# ProcessorBoard_STM32F103C.net
KiCad netlist of a schematic drawn in Altium Designer
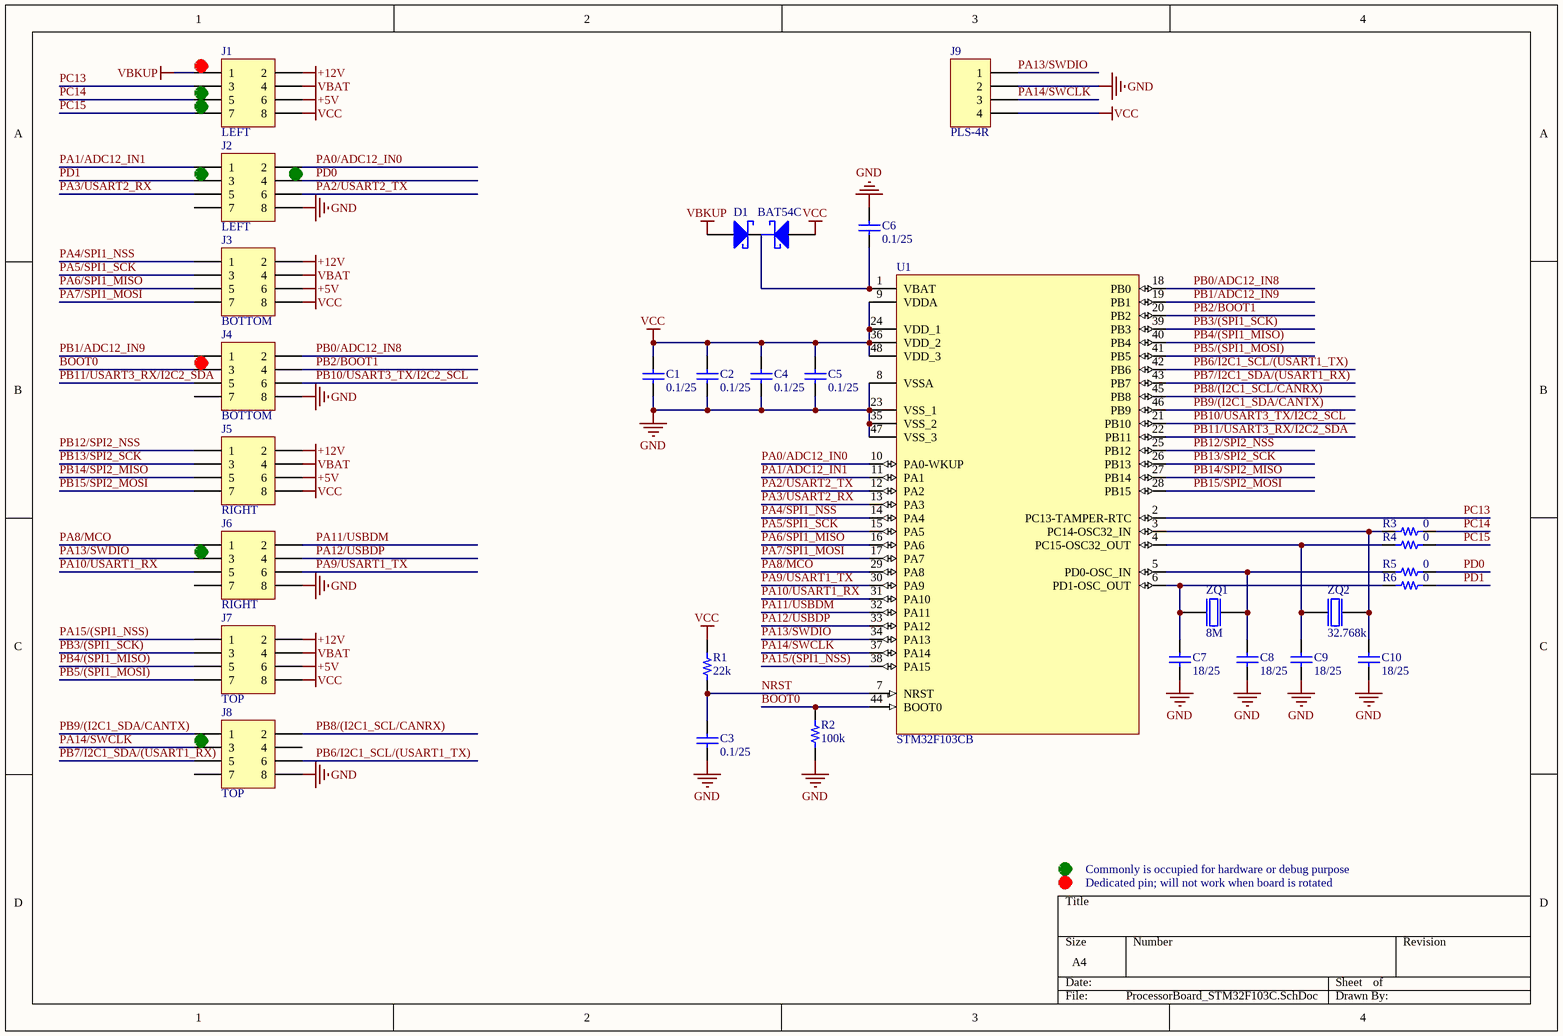
[diagram p0: ProcessorBoard_STM32F103C.SchDoc]

(export (version "E")
  (design (tool "Eeschema 10.0.6"))
  (components
    (comp (ref "C1")
      (value "0.1/25")
      (footprint "CAP0402")
      (description "Ceramic chip capacitor 0402")
      (fields
        (field (name "PARTNUMBER") "CAP0402")
        (field (name "VOLTAGE") "25")
        (field (name "AUTHOR") "oiezhov")
      )
      (libsource (lib "Library") (part "Capacitor"))
    )
    (comp (ref "C2")
      (value "0.1/25")
      (footprint "CAP0402")
      (description "Ceramic chip capacitor 0402")
      (fields
        (field (name "PARTNUMBER") "CAP0402")
        (field (name "VOLTAGE") "25")
        (field (name "AUTHOR") "oiezhov")
      )
      (libsource (lib "Library") (part "Capacitor"))
    )
    (comp (ref "C3")
      (value "0.1/25")
      (footprint "CAP0402")
      (description "Ceramic chip capacitor 0402")
      (fields
        (field (name "PARTNUMBER") "CAP0402")
        (field (name "VOLTAGE") "25")
        (field (name "AUTHOR") "oiezhov")
      )
      (libsource (lib "Library") (part "Capacitor"))
    )
    (comp (ref "C4")
      (value "0.1/25")
      (footprint "CAP0402")
      (description "Ceramic chip capacitor 0402")
      (fields
        (field (name "PARTNUMBER") "CAP0402")
        (field (name "VOLTAGE") "25")
        (field (name "AUTHOR") "oiezhov")
      )
      (libsource (lib "Library") (part "Capacitor"))
    )
    (comp (ref "C5")
      (value "0.1/25")
      (footprint "CAP0402")
      (description "Ceramic chip capacitor 0402")
      (fields
        (field (name "PARTNUMBER") "CAP0402")
        (field (name "VOLTAGE") "25")
        (field (name "AUTHOR") "oiezhov")
      )
      (libsource (lib "Library") (part "Capacitor"))
    )
    (comp (ref "C6")
      (value "0.1/25")
      (footprint "CAP0402")
      (description "Ceramic chip capacitor 0402")
      (fields
        (field (name "PARTNUMBER") "CAP0402")
        (field (name "VOLTAGE") "25")
        (field (name "AUTHOR") "oiezhov")
      )
      (libsource (lib "Library") (part "Capacitor"))
    )
    (comp (ref "C7")
      (value "18/25")
      (footprint "CAP0402")
      (description "Ceramic chip capacitor 0402")
      (fields
        (field (name "PARTNUMBER") "CAP0402")
        (field (name "VOLTAGE") "25")
        (field (name "AUTHOR") "oiezhov")
      )
      (libsource (lib "Library") (part "Capacitor"))
    )
    (comp (ref "C8")
      (value "18/25")
      (footprint "CAP0402")
      (description "Ceramic chip capacitor 0402")
      (fields
        (field (name "PARTNUMBER") "CAP0402")
        (field (name "VOLTAGE") "25")
        (field (name "AUTHOR") "oiezhov")
      )
      (libsource (lib "Library") (part "Capacitor"))
    )
    (comp (ref "C9")
      (value "18/25")
      (footprint "CAP0402")
      (description "Ceramic chip capacitor 0402")
      (fields
        (field (name "PARTNUMBER") "CAP0402")
        (field (name "VOLTAGE") "25")
        (field (name "AUTHOR") "oiezhov")
      )
      (libsource (lib "Library") (part "Capacitor"))
    )
    (comp (ref "C10")
      (value "18/25")
      (footprint "CAP0402")
      (description "Ceramic chip capacitor 0402")
      (fields
        (field (name "PARTNUMBER") "CAP0402")
        (field (name "VOLTAGE") "25")
        (field (name "AUTHOR") "oiezhov")
      )
      (libsource (lib "Library") (part "Capacitor"))
    )
    (comp (ref "D1")
      (value "BAT54C")
      (footprint "SOT23")
      (description "Schottky diode")
      (fields (field (name "AUTHOR") "oiezhov"))
      (libsource (lib "Library") (part "2x Schottky (A-CC-A)"))
    )
    (comp (ref "J1")
      (value "LEFT")
      (footprint "PBDM-8")
      (description "2x4-pin header, pitch 2.54 mm")
      (fields (field (name "PARTNUMBER") "PBDM-8") (field (name "AUTHOR") "oiezhov"))
      (libsource (lib "Library") (part "8-pin dual row connector"))
    )
    (comp (ref "J2")
      (value "LEFT")
      (footprint "PBDM-8")
      (description "2x4-pin header, pitch 2.54 mm")
      (fields (field (name "PARTNUMBER") "PBDM-8") (field (name "AUTHOR") "oiezhov"))
      (libsource (lib "Library") (part "8-pin dual row connector"))
    )
    (comp (ref "J3")
      (value "BOTTOM")
      (footprint "PBDM-8")
      (description "2x4-pin header, pitch 2.54 mm")
      (fields (field (name "PARTNUMBER") "PBDM-8") (field (name "AUTHOR") "oiezhov"))
      (libsource (lib "Library") (part "8-pin dual row connector"))
    )
    (comp (ref "J4")
      (value "BOTTOM")
      (footprint "PBDM-8")
      (description "2x4-pin header, pitch 2.54 mm")
      (fields (field (name "PARTNUMBER") "PBDM-8") (field (name "AUTHOR") "oiezhov"))
      (libsource (lib "Library") (part "8-pin dual row connector"))
    )
    (comp (ref "J5")
      (value "RIGHT")
      (footprint "PBDM-8")
      (description "2x4-pin header, pitch 2.54 mm")
      (fields (field (name "PARTNUMBER") "PBDM-8") (field (name "AUTHOR") "oiezhov"))
      (libsource (lib "Library") (part "8-pin dual row connector"))
    )
    (comp (ref "J6")
      (value "RIGHT")
      (footprint "PBDM-8")
      (description "2x4-pin header, pitch 2.54 mm")
      (fields (field (name "PARTNUMBER") "PBDM-8") (field (name "AUTHOR") "oiezhov"))
      (libsource (lib "Library") (part "8-pin dual row connector"))
    )
    (comp (ref "J7")
      (value "TOP")
      (footprint "PBDM-8")
      (description "2x4-pin header, pitch 2.54 mm")
      (fields (field (name "PARTNUMBER") "PBDM-8") (field (name "AUTHOR") "oiezhov"))
      (libsource (lib "Library") (part "8-pin dual row connector"))
    )
    (comp (ref "J8")
      (value "TOP")
      (footprint "PBDM-8")
      (description "2x4-pin header, pitch 2.54 mm")
      (fields (field (name "PARTNUMBER") "PBDM-8") (field (name "AUTHOR") "oiezhov"))
      (libsource (lib "Library") (part "8-pin dual row connector"))
    )
    (comp (ref "J9")
      (value "PLS-4R")
      (footprint "PLS-4R")
      (description "4-pin angle header, pitch 2.54 mm")
      (fields (field (name "AUTHOR") "oiezhov"))
      (libsource (lib "Library") (part "4-pin connector"))
    )
    (comp (ref "R1")
      (value "22k")
      (footprint "RES0402")
      (description "Ceramic chip resistor")
      (fields (field (name "PARTNUMBER") "RES0402") (field (name "AUTHOR") "oiezhov"))
      (libsource (lib "Library") (part "Resistor"))
    )
    (comp (ref "R2")
      (value "100k")
      (footprint "RES0402")
      (description "Ceramic chip resistor")
      (fields (field (name "PARTNUMBER") "RES0402") (field (name "AUTHOR") "oiezhov"))
      (libsource (lib "Library") (part "Resistor"))
    )
    (comp (ref "R3")
      (value "0")
      (footprint "RES0402")
      (description "Ceramic chip resistor")
      (fields (field (name "PARTNUMBER") "RES0402") (field (name "AUTHOR") "oiezhov"))
      (libsource (lib "Library") (part "Resistor"))
    )
    (comp (ref "R4")
      (value "0")
      (footprint "RES0402")
      (description "Ceramic chip resistor")
      (fields (field (name "PARTNUMBER") "RES0402") (field (name "AUTHOR") "oiezhov"))
      (libsource (lib "Library") (part "Resistor"))
    )
    (comp (ref "R5")
      (value "0")
      (footprint "RES0402")
      (description "Ceramic chip resistor")
      (fields (field (name "PARTNUMBER") "RES0402") (field (name "AUTHOR") "oiezhov"))
      (libsource (lib "Library") (part "Resistor"))
    )
    (comp (ref "R6")
      (value "0")
      (footprint "RES0402")
      (description "Ceramic chip resistor")
      (fields (field (name "PARTNUMBER") "RES0402") (field (name "AUTHOR") "oiezhov"))
      (libsource (lib "Library") (part "Resistor"))
    )
    (comp (ref "U1")
      (value "STM32F103CB")
      (footprint "LQFP48")
      (description "General purpose 32-bit microcontroller")
      (fields (field (name "AUTHOR") "oiezhov"))
      (libsource (lib "Library") (part "STM32F103C"))
    )
    (comp (ref "ZQ1")
      (value "8M")
      (footprint "HC49/U3H")
      (description "Quartz crystal in low profile package")
      (fields (field (name "PARTNUMBER") "KX-3H") (field (name "AUTHOR") "oiezhov"))
      (libsource (lib "Library") (part "Quartz crystal"))
    )
    (comp (ref "ZQ2")
      (value "32.768k")
      (footprint "D6.2x2")
      (description "Quartz crystal in cylindrical package")
      (fields (field (name "PARTNUMBER") "KX-26") (field (name "AUTHOR") "oiezhov"))
      (libsource (lib "Library") (part "Quartz crystal"))
    )
  )
  (nets
    (net (code "1") (name "+5V") (class "Default")
      (node (ref "J1") (pin "6") (pinfunction "6_6") (pintype "passive"))
      (node (ref "J3") (pin "6") (pinfunction "6_6") (pintype "passive"))
      (node (ref "J5") (pin "6") (pinfunction "6_6") (pintype "passive"))
      (node (ref "J7") (pin "6") (pinfunction "6_6") (pintype "passive"))
    )
    (net (code "2") (name "+12V") (class "Default")
      (node (ref "J1") (pin "2") (pinfunction "2_2") (pintype "passive"))
      (node (ref "J3") (pin "2") (pinfunction "2_2") (pintype "passive"))
      (node (ref "J5") (pin "2") (pinfunction "2_2") (pintype "passive"))
      (node (ref "J7") (pin "2") (pinfunction "2_2") (pintype "passive"))
    )
    (net (code "3") (name "/BOOT0") (class "Default")
      (node (ref "J4") (pin "3") (pinfunction "3_3") (pintype "passive"))
      (node (ref "R2") (pin "2") (pinfunction "2_2") (pintype "passive"))
      (node (ref "U1") (pin "44") (pinfunction "BOOT0_44") (pintype "input"))
    )
    (net (code "4") (name "/NRST") (class "Default")
      (node (ref "C3") (pin "2") (pinfunction "2_2") (pintype "passive"))
      (node (ref "R1") (pin "1") (pinfunction "1_1") (pintype "passive"))
      (node (ref "U1") (pin "7") (pinfunction "NRST_7") (pintype "input"))
    )
    (net (code "5") (name "/PA0{slash}ADC12_IN0") (class "Default")
      (node (ref "J2") (pin "2") (pinfunction "2_2") (pintype "passive"))
      (node (ref "U1") (pin "10") (pinfunction "PA0-WKUP_10") (pintype "bidirectional"))
    )
    (net (code "6") (name "/PA1{slash}ADC12_IN1") (class "Default")
      (node (ref "J2") (pin "1") (pinfunction "1_1") (pintype "passive"))
      (node (ref "U1") (pin "11") (pinfunction "PA1_11") (pintype "bidirectional"))
    )
    (net (code "7") (name "/PA2{slash}USART2_TX") (class "Default")
      (node (ref "J2") (pin "6") (pinfunction "6_6") (pintype "passive"))
      (node (ref "U1") (pin "12") (pinfunction "PA2_12") (pintype "bidirectional"))
    )
    (net (code "8") (name "/PA3{slash}USART2_RX") (class "Default")
      (node (ref "J2") (pin "5") (pinfunction "5_5") (pintype "passive"))
      (node (ref "U1") (pin "13") (pinfunction "PA3_13") (pintype "bidirectional"))
    )
    (net (code "9") (name "/PA4{slash}SPI1_NSS") (class "Default")
      (node (ref "J3") (pin "1") (pinfunction "1_1") (pintype "passive"))
      (node (ref "U1") (pin "14") (pinfunction "PA4_14") (pintype "bidirectional"))
    )
    (net (code "10") (name "/PA5{slash}SPI1_SCK") (class "Default")
      (node (ref "J3") (pin "3") (pinfunction "3_3") (pintype "passive"))
      (node (ref "U1") (pin "15") (pinfunction "PA5_15") (pintype "bidirectional"))
    )
    (net (code "11") (name "/PA6{slash}SPI1_MISO") (class "Default")
      (node (ref "J3") (pin "5") (pinfunction "5_5") (pintype "passive"))
      (node (ref "U1") (pin "16") (pinfunction "PA6_16") (pintype "bidirectional"))
    )
    (net (code "12") (name "/PA7{slash}SPI1_MOSI") (class "Default")
      (node (ref "J3") (pin "7") (pinfunction "7_7") (pintype "passive"))
      (node (ref "U1") (pin "17") (pinfunction "PA7_17") (pintype "bidirectional"))
    )
    (net (code "13") (name "/PA8{slash}MCO") (class "Default")
      (node (ref "J6") (pin "1") (pinfunction "1_1") (pintype "passive"))
      (node (ref "U1") (pin "29") (pinfunction "PA8_29") (pintype "bidirectional"))
    )
    (net (code "14") (name "/PA9{slash}USART1_TX") (class "Default")
      (node (ref "J6") (pin "6") (pinfunction "6_6") (pintype "passive"))
      (node (ref "U1") (pin "30") (pinfunction "PA9_30") (pintype "bidirectional"))
    )
    (net (code "15") (name "/PA10{slash}USART1_RX") (class "Default")
      (node (ref "J6") (pin "5") (pinfunction "5_5") (pintype "passive"))
      (node (ref "U1") (pin "31") (pinfunction "PA10_31") (pintype "bidirectional"))
    )
    (net (code "16") (name "/PA11{slash}USBDM") (class "Default")
      (node (ref "J6") (pin "2") (pinfunction "2_2") (pintype "passive"))
      (node (ref "U1") (pin "32") (pinfunction "PA11_32") (pintype "bidirectional"))
    )
    (net (code "17") (name "/PA12{slash}USBDP") (class "Default")
      (node (ref "J6") (pin "4") (pinfunction "4_4") (pintype "passive"))
      (node (ref "U1") (pin "33") (pinfunction "PA12_33") (pintype "bidirectional"))
    )
    (net (code "18") (name "/PA13{slash}SWDIO") (class "Default")
      (node (ref "J6") (pin "3") (pinfunction "3_3") (pintype "passive"))
      (node (ref "J9") (pin "1") (pinfunction "1_1") (pintype "passive"))
      (node (ref "U1") (pin "34") (pinfunction "PA13_34") (pintype "bidirectional"))
    )
    (net (code "19") (name "/PA14{slash}SWCLK") (class "Default")
      (node (ref "J8") (pin "3") (pinfunction "3_3") (pintype "passive"))
      (node (ref "J9") (pin "3") (pinfunction "3_3") (pintype "passive"))
      (node (ref "U1") (pin "37") (pinfunction "PA14_37") (pintype "bidirectional"))
    )
    (net (code "20") (name "/PA15{slash}(SPI1_NSS)") (class "Default")
      (node (ref "J7") (pin "1") (pinfunction "1_1") (pintype "passive"))
      (node (ref "U1") (pin "38") (pinfunction "PA15_38") (pintype "bidirectional"))
    )
    (net (code "21") (name "/PB0{slash}ADC12_IN8") (class "Default")
      (node (ref "J4") (pin "2") (pinfunction "2_2") (pintype "passive"))
      (node (ref "U1") (pin "18") (pinfunction "PB0_18") (pintype "bidirectional"))
    )
    (net (code "22") (name "/PB1{slash}ADC12_IN9") (class "Default")
      (node (ref "J4") (pin "1") (pinfunction "1_1") (pintype "passive"))
      (node (ref "U1") (pin "19") (pinfunction "PB1_19") (pintype "bidirectional"))
    )
    (net (code "23") (name "/PB2{slash}BOOT1") (class "Default")
      (node (ref "J4") (pin "4") (pinfunction "4_4") (pintype "passive"))
      (node (ref "U1") (pin "20") (pinfunction "PB2_20") (pintype "bidirectional"))
    )
    (net (code "24") (name "/PB3{slash}(SPI1_SCK)") (class "Default")
      (node (ref "J7") (pin "3") (pinfunction "3_3") (pintype "passive"))
      (node (ref "U1") (pin "39") (pinfunction "PB3_39") (pintype "bidirectional"))
    )
    (net (code "25") (name "/PB4{slash}(SPI1_MISO)") (class "Default")
      (node (ref "J7") (pin "5") (pinfunction "5_5") (pintype "passive"))
      (node (ref "U1") (pin "40") (pinfunction "PB4_40") (pintype "bidirectional"))
    )
    (net (code "26") (name "/PB5{slash}(SPI1_MOSI)") (class "Default")
      (node (ref "J7") (pin "7") (pinfunction "7_7") (pintype "passive"))
      (node (ref "U1") (pin "41") (pinfunction "PB5_41") (pintype "bidirectional"))
    )
    (net (code "27") (name "/PB6{slash}I2C1_SCL{slash}(USART1_TX)") (class "Default")
      (node (ref "J8") (pin "6") (pinfunction "6_6") (pintype "passive"))
      (node (ref "U1") (pin "42") (pinfunction "PB6_42") (pintype "bidirectional"))
    )
    (net (code "28") (name "/PB7{slash}I2C1_SDA{slash}(USART1_RX)") (class "Default")
      (node (ref "J8") (pin "5") (pinfunction "5_5") (pintype "passive"))
      (node (ref "U1") (pin "43") (pinfunction "PB7_43") (pintype "bidirectional"))
    )
    (net (code "29") (name "/PB8{slash}(I2C1_SCL{slash}CANRX)") (class "Default")
      (node (ref "J8") (pin "2") (pinfunction "2_2") (pintype "passive"))
      (node (ref "U1") (pin "45") (pinfunction "PB8_45") (pintype "bidirectional"))
    )
    (net (code "30") (name "/PB9{slash}(I2C1_SDA{slash}CANTX)") (class "Default")
      (node (ref "J8") (pin "1") (pinfunction "1_1") (pintype "passive"))
      (node (ref "U1") (pin "46") (pinfunction "PB9_46") (pintype "bidirectional"))
    )
    (net (code "31") (name "/PB10{slash}USART3_TX{slash}I2C2_SCL") (class "Default")
      (node (ref "J4") (pin "6") (pinfunction "6_6") (pintype "passive"))
      (node (ref "U1") (pin "21") (pinfunction "PB10_21") (pintype "bidirectional"))
    )
    (net (code "32") (name "/PB11{slash}USART3_RX{slash}I2C2_SDA") (class "Default")
      (node (ref "J4") (pin "5") (pinfunction "5_5") (pintype "passive"))
      (node (ref "U1") (pin "22") (pinfunction "PB11_22") (pintype "bidirectional"))
    )
    (net (code "33") (name "/PB12{slash}SPI2_NSS") (class "Default")
      (node (ref "J5") (pin "1") (pinfunction "1_1") (pintype "passive"))
      (node (ref "U1") (pin "25") (pinfunction "PB12_25") (pintype "bidirectional"))
    )
    (net (code "34") (name "/PB13{slash}SPI2_SCK") (class "Default")
      (node (ref "J5") (pin "3") (pinfunction "3_3") (pintype "passive"))
      (node (ref "U1") (pin "26") (pinfunction "PB13_26") (pintype "bidirectional"))
    )
    (net (code "35") (name "/PB14{slash}SPI2_MISO") (class "Default")
      (node (ref "J5") (pin "5") (pinfunction "5_5") (pintype "passive"))
      (node (ref "U1") (pin "27") (pinfunction "PB14_27") (pintype "bidirectional"))
    )
    (net (code "36") (name "/PB15{slash}SPI2_MOSI") (class "Default")
      (node (ref "J5") (pin "7") (pinfunction "7_7") (pintype "passive"))
      (node (ref "U1") (pin "28") (pinfunction "PB15_28") (pintype "bidirectional"))
    )
    (net (code "37") (name "/PC13") (class "Default")
      (node (ref "J1") (pin "3") (pinfunction "3_3") (pintype "passive"))
      (node (ref "U1") (pin "2") (pinfunction "PC13-TAMPER-RTC_2") (pintype "bidirectional"))
    )
    (net (code "38") (name "/PC14") (class "Default")
      (node (ref "J1") (pin "5") (pinfunction "5_5") (pintype "passive"))
      (node (ref "R3") (pin "1") (pinfunction "1_1") (pintype "passive"))
    )
    (net (code "39") (name "/PC15") (class "Default")
      (node (ref "J1") (pin "7") (pinfunction "7_7") (pintype "passive"))
      (node (ref "R4") (pin "1") (pinfunction "1_1") (pintype "passive"))
    )
    (net (code "40") (name "/PD0") (class "Default")
      (node (ref "J2") (pin "4") (pinfunction "4_4") (pintype "passive"))
      (node (ref "R5") (pin "1") (pinfunction "1_1") (pintype "passive"))
    )
    (net (code "41") (name "/PD1") (class "Default")
      (node (ref "J2") (pin "3") (pinfunction "3_3") (pintype "passive"))
      (node (ref "R6") (pin "1") (pinfunction "1_1") (pintype "passive"))
    )
    (net (code "42") (name "GND") (class "Default")
      (node (ref "C1") (pin "1") (pinfunction "1_1") (pintype "passive"))
      (node (ref "C10") (pin "1") (pinfunction "1_1") (pintype "passive"))
      (node (ref "C2") (pin "1") (pinfunction "1_1") (pintype "passive"))
      (node (ref "C3") (pin "1") (pinfunction "1_1") (pintype "passive"))
      (node (ref "C4") (pin "1") (pinfunction "1_1") (pintype "passive"))
      (node (ref "C5") (pin "1") (pinfunction "1_1") (pintype "passive"))
      (node (ref "C6") (pin "1") (pinfunction "1_1") (pintype "passive"))
      (node (ref "C7") (pin "1") (pinfunction "1_1") (pintype "passive"))
      (node (ref "C8") (pin "1") (pinfunction "1_1") (pintype "passive"))
      (node (ref "C9") (pin "1") (pinfunction "1_1") (pintype "passive"))
      (node (ref "J2") (pin "8") (pinfunction "8_8") (pintype "passive"))
      (node (ref "J4") (pin "8") (pinfunction "8_8") (pintype "passive"))
      (node (ref "J6") (pin "8") (pinfunction "8_8") (pintype "passive"))
      (node (ref "J8") (pin "8") (pinfunction "8_8") (pintype "passive"))
      (node (ref "J9") (pin "2") (pinfunction "2_2") (pintype "passive"))
      (node (ref "R2") (pin "1") (pinfunction "1_1") (pintype "passive"))
      (node (ref "U1") (pin "23") (pinfunction "VSS_1_23") (pintype "power_in"))
      (node (ref "U1") (pin "35") (pinfunction "VSS_2_35") (pintype "power_in"))
      (node (ref "U1") (pin "47") (pinfunction "VSS_3_47") (pintype "power_in"))
      (node (ref "U1") (pin "8") (pinfunction "VSSA_8") (pintype "power_in"))
    )
    (net (code "43") (name "Net-(U1-PC14-OSC32_IN)") (class "Default")
      (node (ref "C10") (pin "2") (pinfunction "2_2") (pintype "passive"))
      (node (ref "R3") (pin "2") (pinfunction "2_2") (pintype "passive"))
      (node (ref "U1") (pin "3") (pinfunction "PC14-OSC32_IN_3") (pintype "bidirectional"))
      (node (ref "ZQ2") (pin "2") (pinfunction "2_2") (pintype "passive"))
    )
    (net (code "44") (name "Net-(U1-PC15-OSC32_OUT)") (class "Default")
      (node (ref "C9") (pin "2") (pinfunction "2_2") (pintype "passive"))
      (node (ref "R4") (pin "2") (pinfunction "2_2") (pintype "passive"))
      (node (ref "U1") (pin "4") (pinfunction "PC15-OSC32_OUT_4") (pintype "bidirectional"))
      (node (ref "ZQ2") (pin "1") (pinfunction "1_1") (pintype "passive"))
    )
    (net (code "45") (name "Net-(U1-PD0-OSC_IN)") (class "Default")
      (node (ref "C8") (pin "2") (pinfunction "2_2") (pintype "passive"))
      (node (ref "R5") (pin "2") (pinfunction "2_2") (pintype "passive"))
      (node (ref "U1") (pin "5") (pinfunction "PD0-OSC_IN_5") (pintype "bidirectional"))
      (node (ref "ZQ1") (pin "2") (pinfunction "2_2") (pintype "passive"))
    )
    (net (code "46") (name "Net-(U1-PD1-OSC_OUT)") (class "Default")
      (node (ref "C7") (pin "2") (pinfunction "2_2") (pintype "passive"))
      (node (ref "R6") (pin "2") (pinfunction "2_2") (pintype "passive"))
      (node (ref "U1") (pin "6") (pinfunction "PD1-OSC_OUT_6") (pintype "bidirectional"))
      (node (ref "ZQ1") (pin "1") (pinfunction "1_1") (pintype "passive"))
    )
    (net (code "47") (name "Net-(U1-VBAT)") (class "Default")
      (node (ref "C6") (pin "2") (pinfunction "2_2") (pintype "passive"))
      (node (ref "D1") (pin "3") (pinfunction "3_3") (pintype "passive"))
      (node (ref "U1") (pin "1") (pinfunction "VBAT_1") (pintype "power_in"))
    )
    (net (code "48") (name "VBAT") (class "Default")
      (node (ref "J1") (pin "4") (pinfunction "4_4") (pintype "passive"))
      (node (ref "J3") (pin "4") (pinfunction "4_4") (pintype "passive"))
      (node (ref "J5") (pin "4") (pinfunction "4_4") (pintype "passive"))
      (node (ref "J7") (pin "4") (pinfunction "4_4") (pintype "passive"))
    )
    (net (code "49") (name "VBKUP") (class "Default")
      (node (ref "D1") (pin "1") (pinfunction "1_1") (pintype "passive"))
      (node (ref "J1") (pin "1") (pinfunction "1_1") (pintype "passive"))
    )
    (net (code "50") (name "VCC") (class "Default")
      (node (ref "C1") (pin "2") (pinfunction "2_2") (pintype "passive"))
      (node (ref "C2") (pin "2") (pinfunction "2_2") (pintype "passive"))
      (node (ref "C4") (pin "2") (pinfunction "2_2") (pintype "passive"))
      (node (ref "C5") (pin "2") (pinfunction "2_2") (pintype "passive"))
      (node (ref "D1") (pin "2") (pinfunction "2_2") (pintype "passive"))
      (node (ref "J1") (pin "8") (pinfunction "8_8") (pintype "passive"))
      (node (ref "J3") (pin "8") (pinfunction "8_8") (pintype "passive"))
      (node (ref "J5") (pin "8") (pinfunction "8_8") (pintype "passive"))
      (node (ref "J7") (pin "8") (pinfunction "8_8") (pintype "passive"))
      (node (ref "J9") (pin "4") (pinfunction "4_4") (pintype "passive"))
      (node (ref "R1") (pin "2") (pinfunction "2_2") (pintype "passive"))
      (node (ref "U1") (pin "24") (pinfunction "VDD_1_24") (pintype "power_in"))
      (node (ref "U1") (pin "36") (pinfunction "VDD_2_36") (pintype "power_in"))
      (node (ref "U1") (pin "48") (pinfunction "VDD_3_48") (pintype "power_in"))
      (node (ref "U1") (pin "9") (pinfunction "VDDA_9") (pintype "power_in"))
    )
    (net (code "51") (name "unconnected-(J2-Pad7)") (class "Default")
      (node (ref "J2") (pin "7") (pinfunction "7_7") (pintype "passive"))
    )
    (net (code "52") (name "unconnected-(J4-Pad7)") (class "Default")
      (node (ref "J4") (pin "7") (pinfunction "7_7") (pintype "passive"))
    )
    (net (code "53") (name "unconnected-(J6-Pad7)") (class "Default")
      (node (ref "J6") (pin "7") (pinfunction "7_7") (pintype "passive"))
    )
    (net (code "54") (name "unconnected-(J8-Pad4)") (class "Default")
      (node (ref "J8") (pin "4") (pinfunction "4_4") (pintype "passive"))
    )
    (net (code "55") (name "unconnected-(J8-Pad7)") (class "Default")
      (node (ref "J8") (pin "7") (pinfunction "7_7") (pintype "passive"))
    )
  )
)
